# Reefing-BM.net
KiCad netlist of a schematic drawn in Altium Designer
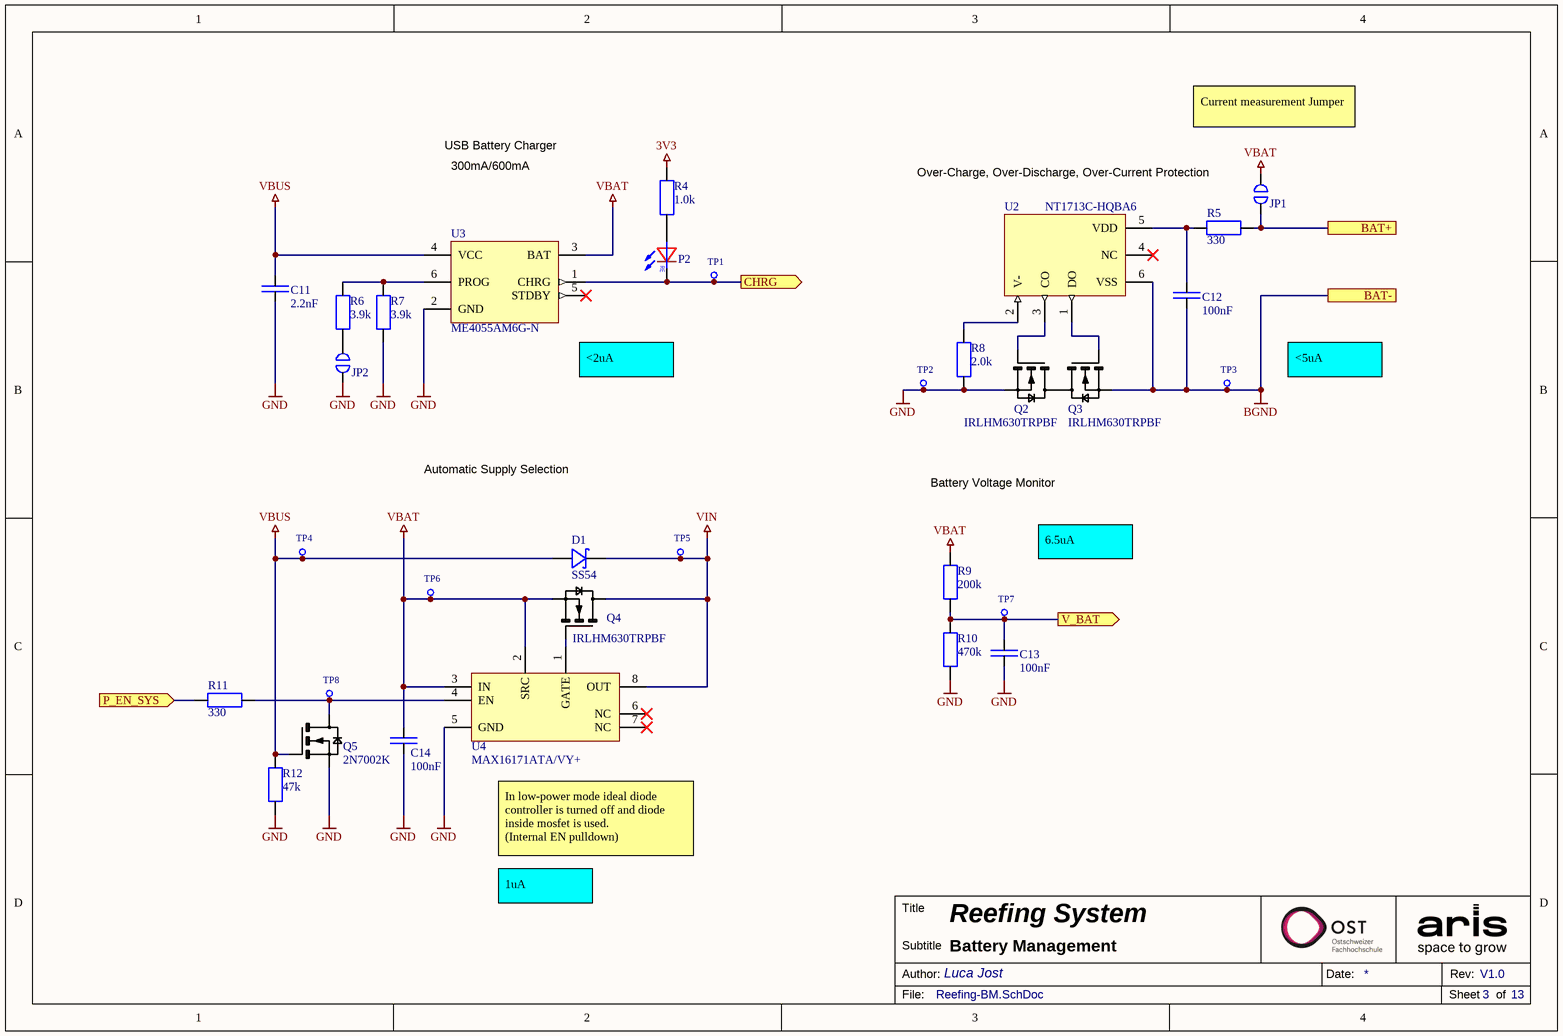
[diagram p0: Reefing-BM.SchDoc]

(export (version "E")
  (design (tool "Eeschema 10.0.6"))
  (components
    (comp (ref "C11")
      (value "2.2nF")
      (footprint "SMD Keramikkondensator 0805")
      (description "SMD Ceramic Capacitor E6")
      (libsource (lib "Ceramic Capacitors-E6") (part "E6 - 2.2nF"))
    )
    (comp (ref "C12")
      (value "100nF")
      (footprint "SMD Keramikkondensator 0805")
      (description "SMD Ceramic Capacitor E6")
      (libsource (lib "Ceramic Capacitors-E6") (part "E6 - 100nF"))
    )
    (comp (ref "C13")
      (value "100nF")
      (footprint "SMD Keramikkondensator 0805")
      (description "SMD Ceramic Capacitor E6")
      (libsource (lib "Ceramic Capacitors-E6") (part "E6 - 100nF"))
    )
    (comp (ref "C14")
      (value "100nF")
      (footprint "SMD Keramikkondensator 0805")
      (description "SMD Ceramic Capacitor E6")
      (libsource (lib "Ceramic Capacitors-E6") (part "E6 - 100nF"))
    )
    (comp (ref "D1")
      (value "SS54")
      (footprint "SMD Diode DO-214-AC")
      (description "40V 5A 550mV @ 5A SMA(DO-214AC) Schottky Barrier Diodes (SBD) ROHS")
      (libsource (lib "Diodes") (part "SS54"))
    )
    (comp (ref "JP1")
      (value "Jumper")
      (footprint "SMD Solder Jumper 1x2mm")
      (description "Single Position Jumper")
      (libsource (lib "Connectors") (part "Jumper-1"))
    )
    (comp (ref "JP2")
      (value "Jumper")
      (footprint "SMD Solder Jumper 1x2mm")
      (description "Single Position Jumper")
      (libsource (lib "Connectors") (part "Jumper-1"))
    )
    (comp (ref "P2")
      (value "LED")
      (footprint "SMD LED 0603")
      (description "Color LED")
      (libsource (lib "Diodes") (part "LED"))
    )
    (comp (ref "Q2")
      (value "IRLHM630TRPBF")
      (footprint "SMD MOSFET DFN 3x3 EP")
      (description "N-Channel 30V 21A 3.5mOhm@4.5V")
      (libsource (lib "") (part "IRLHM630TRPBF_1"))
    )
    (comp (ref "Q3")
      (value "IRLHM630TRPBF")
      (footprint "SMD MOSFET DFN 3x3 EP")
      (description "N-Channel 30V 21A 3.5mOhm@4.5V")
      (libsource (lib "Electronic Switches") (part "IRLHM630TRPBF"))
    )
    (comp (ref "Q4")
      (value "IRLHM630TRPBF")
      (footprint "SMD MOSFET DFN 3x3 EP")
      (description "N-Channel 30V 21A 3.5mOhm@4.5V")
      (libsource (lib "") (part "IRLHM630TRPBF_2"))
    )
    (comp (ref "Q5")
      (value "2N7002K")
      (footprint "SMD MOSFET SOT-23")
      (description "MOSFET N-Channel 60V / 500mA")
      (libsource (lib "Electronic Switches") (part "2N7002K"))
    )
    (comp (ref "R4")
      (value "1.0k")
      (footprint "SMD Widerstand 0805")
      (description "SMD Chip Resistor E24")
      (libsource (lib "Resistors-E24") (part "E24 - 1.0k"))
    )
    (comp (ref "R5")
      (value "330")
      (footprint "SMD Widerstand 0805")
      (description "SMD Chip Resistor E24")
      (libsource (lib "Resistors-E24") (part "E24 - 330"))
    )
    (comp (ref "R6")
      (value "3.9k")
      (footprint "SMD Widerstand 0805")
      (description "SMD Chip Resistor E24")
      (libsource (lib "Resistors-E24") (part "E24 - 3.9k"))
    )
    (comp (ref "R7")
      (value "3.9k")
      (footprint "SMD Widerstand 0805")
      (description "SMD Chip Resistor E24")
      (libsource (lib "Resistors-E24") (part "E24 - 3.9k"))
    )
    (comp (ref "R8")
      (value "2.0k")
      (footprint "SMD Widerstand 0805")
      (description "SMD Chip Resistor E96")
      (libsource (lib "Resistors-E96") (part "E96 - 2.0k"))
    )
    (comp (ref "R9")
      (value "200k")
      (footprint "SMD Widerstand 0805")
      (description "SMD Chip Resistor E24")
      (libsource (lib "Resistors-E24") (part "E24 - 200k"))
    )
    (comp (ref "R10")
      (value "470k")
      (footprint "SMD Widerstand 0805")
      (description "SMD Chip Resistor E24")
      (libsource (lib "Resistors-E24") (part "E24 - 470k"))
    )
    (comp (ref "R11")
      (value "330")
      (footprint "SMD Widerstand 0805")
      (description "SMD Chip Resistor E24")
      (libsource (lib "Resistors-E24") (part "E24 - 330"))
    )
    (comp (ref "R12")
      (value "47k")
      (footprint "SMD Widerstand 0805")
      (description "SMD Chip Resistor E24")
      (libsource (lib "Resistors-E24") (part "E24 - 47k"))
    )
    (comp (ref "TP1")
      (value "X-TP")
      (footprint "SMD Testpunkt Ø1mm")
      (description "Testpunkt")
      (libsource (lib "Fleet-Monitor") (part "X-TP"))
    )
    (comp (ref "TP2")
      (value "X-TP")
      (footprint "SMD Testpunkt Ø1mm")
      (description "Testpunkt")
      (libsource (lib "Fleet-Monitor") (part "X-TP"))
    )
    (comp (ref "TP3")
      (value "X-TP")
      (footprint "SMD Testpunkt Ø1mm")
      (description "Testpunkt")
      (libsource (lib "Fleet-Monitor") (part "X-TP"))
    )
    (comp (ref "TP4")
      (value "X-TP")
      (footprint "SMD Testpunkt Ø1mm")
      (description "Testpunkt")
      (libsource (lib "Fleet-Monitor") (part "X-TP"))
    )
    (comp (ref "TP5")
      (value "X-TP")
      (footprint "SMD Testpunkt Ø1mm")
      (description "Testpunkt")
      (libsource (lib "Fleet-Monitor") (part "X-TP"))
    )
    (comp (ref "TP6")
      (value "X-TP")
      (footprint "SMD Testpunkt Ø1mm")
      (description "Testpunkt")
      (libsource (lib "Fleet-Monitor") (part "X-TP"))
    )
    (comp (ref "TP7")
      (value "X-TP")
      (footprint "SMD Testpunkt Ø1mm")
      (description "Testpunkt")
      (libsource (lib "Fleet-Monitor") (part "X-TP"))
    )
    (comp (ref "TP8")
      (value "X-TP")
      (footprint "SMD Testpunkt Ø1mm")
      (description "Testpunkt")
      (libsource (lib "Fleet-Monitor") (part "X-TP"))
    )
    (comp (ref "U2")
      (value "NT1713C-HQBA6")
      (footprint "SMD IC SOT-23-6")
      (description "Protection IC for 1-Cell Battery Pack")
      (libsource (lib "Power Management") (part "NT1713C-HQBA6"))
    )
    (comp (ref "U3")
      (value "ME4055AM6G-N")
      (footprint "SMD IC SOT-23-6")
      (description "800mA Lithium Ion Battery Linear Charger")
      (libsource (lib "Voltage-Converter") (part "ME4055AM6G-N"))
    )
    (comp (ref "U4")
      (value "MAX16171ATA/VY+")
      (footprint "SMD IC TDFN-8")
      (description "OR Controller N+1 ORing Controller N-Channel 1:1 8-TDFN-CU (2x3)")
      (libsource (lib "Power Management") (part "MAX16171ATA/VY+"))
    )
  )
  (nets
    (net (code "1") (name "/BAT+") (class "Default")
      (node (ref "JP1") (pin "2") (pintype "passive"))
      (node (ref "R5") (pin "1") (pinfunction "1_1") (pintype "passive"))
    )
    (net (code "2") (name "/CHRG") (class "Default")
      (node (ref "P2") (pin "K") (pinfunction "K_K") (pintype "passive"))
      (node (ref "TP1") (pin "1") (pinfunction "1_1") (pintype "passive"))
      (node (ref "U3") (pin "1") (pinfunction "CHRG_1") (pintype "output"))
    )
    (net (code "3") (name "/P_EN_SYS") (class "Default")
      (node (ref "R11") (pin "2") (pinfunction "2_2") (pintype "passive"))
    )
    (net (code "4") (name "/V_BAT") (class "Default")
      (node (ref "C13") (pin "2") (pinfunction "2_2") (pintype "passive"))
      (node (ref "R10") (pin "2") (pinfunction "2_2") (pintype "passive"))
      (node (ref "R9") (pin "1") (pinfunction "1_1") (pintype "passive"))
      (node (ref "TP7") (pin "1") (pinfunction "1_1") (pintype "passive"))
    )
    (net (code "5") (name "3V3") (class "Default")
      (node (ref "R4") (pin "2") (pinfunction "2_2") (pintype "passive"))
    )
    (net (code "6") (name "BGND") (class "Default")
      (node (ref "C12") (pin "1") (pinfunction "1_1") (pintype "passive"))
      (node (ref "Q3") (pin "S") (pinfunction "S_S") (pintype "passive"))
      (node (ref "TP3") (pin "1") (pinfunction "1_1") (pintype "passive"))
      (node (ref "U2") (pin "6") (pinfunction "VSS_6") (pintype "passive"))
    )
    (net (code "7") (name "GND") (class "Default")
      (node (ref "C11") (pin "1") (pinfunction "1_1") (pintype "passive"))
      (node (ref "C13") (pin "1") (pinfunction "1_1") (pintype "passive"))
      (node (ref "C14") (pin "1") (pinfunction "1_1") (pintype "passive"))
      (node (ref "JP2") (pin "2") (pintype "passive"))
      (node (ref "Q2") (pin "S") (pinfunction "S_S") (pintype "passive"))
      (node (ref "Q5") (pin "S") (pinfunction "S_S") (pintype "passive"))
      (node (ref "R10") (pin "1") (pinfunction "1_1") (pintype "passive"))
      (node (ref "R12") (pin "1") (pinfunction "1_1") (pintype "passive"))
      (node (ref "R7") (pin "1") (pinfunction "1_1") (pintype "passive"))
      (node (ref "R8") (pin "1") (pinfunction "1_1") (pintype "passive"))
      (node (ref "TP2") (pin "1") (pinfunction "1_1") (pintype "passive"))
      (node (ref "U3") (pin "2") (pinfunction "GND_2") (pintype "passive"))
      (node (ref "U4") (pin "5") (pinfunction "GND_5") (pintype "passive"))
    )
    (net (code "8") (name "Net-(JP2-Pad1)") (class "Default")
      (node (ref "JP2") (pin "1") (pintype "passive"))
      (node (ref "R6") (pin "1") (pinfunction "1_1") (pintype "passive"))
    )
    (net (code "9") (name "Net-(P2-PadA)") (class "Default")
      (node (ref "P2") (pin "A") (pinfunction "A_A") (pintype "passive"))
      (node (ref "R4") (pin "1") (pinfunction "1_1") (pintype "passive"))
    )
    (net (code "10") (name "Net-(Q2-PadD)") (class "Default")
      (node (ref "Q2") (pin "D") (pinfunction "D_D") (pintype "passive"))
      (node (ref "Q3") (pin "D") (pinfunction "D_D") (pintype "passive"))
    )
    (net (code "11") (name "Net-(U2-CO)") (class "Default")
      (node (ref "Q2") (pin "G") (pinfunction "G_G") (pintype "passive"))
      (node (ref "U2") (pin "3") (pinfunction "CO_3") (pintype "output"))
    )
    (net (code "12") (name "Net-(U2-DO)") (class "Default")
      (node (ref "Q3") (pin "G") (pinfunction "G_G") (pintype "passive"))
      (node (ref "U2") (pin "1") (pinfunction "DO_1") (pintype "output"))
    )
    (net (code "13") (name "Net-(U2-V-)") (class "Default")
      (node (ref "R8") (pin "2") (pinfunction "2_2") (pintype "passive"))
      (node (ref "U2") (pin "2") (pinfunction "V-_2") (pintype "input"))
    )
    (net (code "14") (name "Net-(U2-VDD)") (class "Default")
      (node (ref "C12") (pin "2") (pinfunction "2_2") (pintype "passive"))
      (node (ref "R5") (pin "2") (pinfunction "2_2") (pintype "passive"))
      (node (ref "U2") (pin "5") (pinfunction "VDD_5") (pintype "passive"))
    )
    (net (code "15") (name "Net-(U3-PROG)") (class "Default")
      (node (ref "R6") (pin "2") (pinfunction "2_2") (pintype "passive"))
      (node (ref "R7") (pin "2") (pinfunction "2_2") (pintype "passive"))
      (node (ref "U3") (pin "6") (pinfunction "PROG_6") (pintype "passive"))
    )
    (net (code "16") (name "Net-(U4-EN)") (class "Default")
      (node (ref "Q5") (pin "D") (pinfunction "D_D") (pintype "passive"))
      (node (ref "R11") (pin "1") (pinfunction "1_1") (pintype "passive"))
      (node (ref "TP8") (pin "1") (pinfunction "1_1") (pintype "passive"))
      (node (ref "U4") (pin "4") (pinfunction "EN_4") (pintype "passive"))
    )
    (net (code "17") (name "Net-(U4-GATE)") (class "Default")
      (node (ref "Q4") (pin "G") (pinfunction "G_G") (pintype "passive"))
      (node (ref "U4") (pin "1") (pinfunction "GATE_1") (pintype "passive"))
    )
    (net (code "18") (name "VBAT") (class "Default")
      (node (ref "C14") (pin "2") (pinfunction "2_2") (pintype "passive"))
      (node (ref "JP1") (pin "1") (pintype "passive"))
      (node (ref "Q4") (pin "S") (pinfunction "S_S") (pintype "passive"))
      (node (ref "R9") (pin "2") (pinfunction "2_2") (pintype "passive"))
      (node (ref "TP6") (pin "1") (pinfunction "1_1") (pintype "passive"))
      (node (ref "U3") (pin "3") (pinfunction "BAT_3") (pintype "passive"))
      (node (ref "U4") (pin "2") (pinfunction "SRC_2") (pintype "passive"))
      (node (ref "U4") (pin "3") (pinfunction "IN_3") (pintype "passive"))
    )
    (net (code "19") (name "VBUS") (class "Default")
      (node (ref "C11") (pin "2") (pinfunction "2_2") (pintype "passive"))
      (node (ref "D1") (pin "A") (pinfunction "A_A") (pintype "passive"))
      (node (ref "Q5") (pin "G") (pinfunction "G_G") (pintype "passive"))
      (node (ref "R12") (pin "2") (pinfunction "2_2") (pintype "passive"))
      (node (ref "TP4") (pin "1") (pinfunction "1_1") (pintype "passive"))
      (node (ref "U3") (pin "4") (pinfunction "VCC_4") (pintype "passive"))
    )
    (net (code "20") (name "VIN") (class "Default")
      (node (ref "D1") (pin "K") (pinfunction "K_K") (pintype "passive"))
      (node (ref "Q4") (pin "D") (pinfunction "D_D") (pintype "passive"))
      (node (ref "TP5") (pin "1") (pinfunction "1_1") (pintype "passive"))
      (node (ref "U4") (pin "8") (pinfunction "OUT_8") (pintype "passive"))
    )
    (net (code "21") (name "unconnected-(U2-NC-Pad4)") (class "Default")
      (node (ref "U2") (pin "4") (pinfunction "NC_4") (pintype "passive+no_connect"))
    )
    (net (code "22") (name "unconnected-(U3-STDBY-Pad5)") (class "Default")
      (node (ref "U3") (pin "5") (pinfunction "STDBY_5") (pintype "output+no_connect"))
    )
    (net (code "23") (name "unconnected-(U4-NC-Pad6)") (class "Default")
      (node (ref "U4") (pin "6") (pinfunction "NC_6") (pintype "passive+no_connect"))
    )
    (net (code "24") (name "unconnected-(U4-NC-Pad7)") (class "Default")
      (node (ref "U4") (pin "7") (pinfunction "NC_7") (pintype "passive+no_connect"))
    )
  )
)
